# MegaShield-Teensy356-Carrier-v1_0.net
KiCad netlist of a schematic drawn in EAGLE
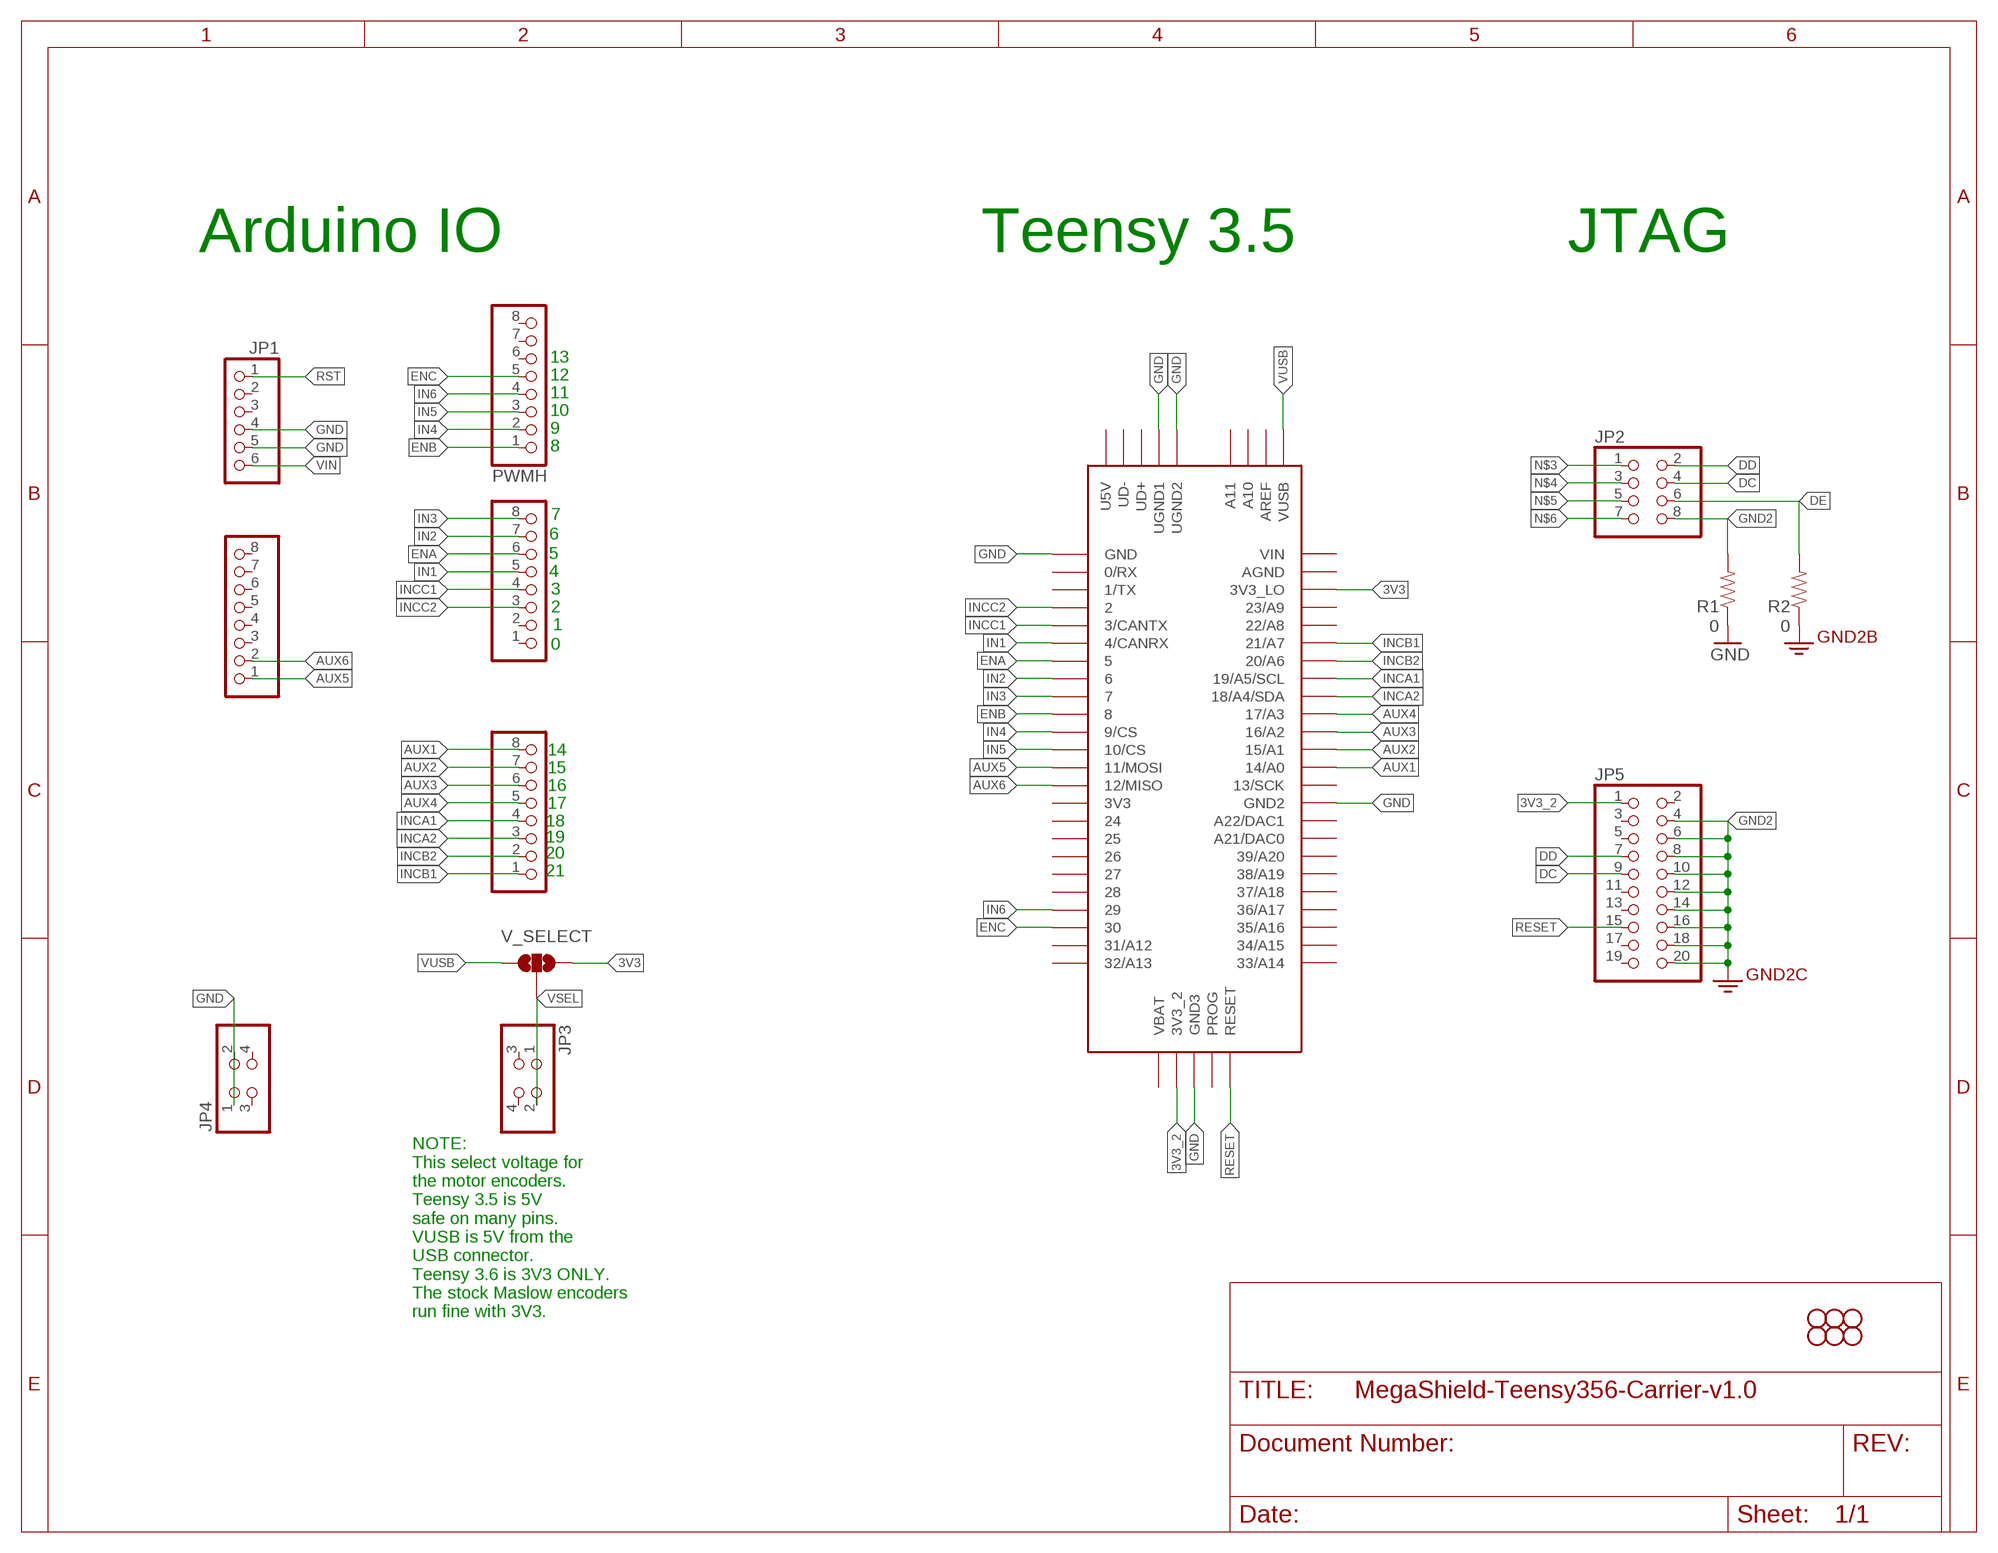
[diagram p0: schematic, sheet 1]

(export (version "E")
  (design (tool "Eeschema 10.0.6"))
  (components
    (comp (ref "COMMUNICATION")
      (value "PINHD-1X8")
      (footprint "eagle-import:1X08")
      (libsource (lib "eagle-import") (part "PINHD-1X8"))
    )
    (comp (ref "COMMUNICATION1")
      (value "PINHD-1X8")
      (footprint "eagle-import:1X08")
      (libsource (lib "eagle-import") (part "PINHD-1X8"))
    )
    (comp (ref "H1")
      (value "STAND-OFF")
      (footprint "eagle-import:STAND-OFF")
      (libsource (lib "eagle-import") (part "STAND-OFF"))
    )
    (comp (ref "H2")
      (value "STAND-OFF")
      (footprint "eagle-import:STAND-OFF")
      (libsource (lib "eagle-import") (part "STAND-OFF"))
    )
    (comp (ref "H3")
      (value "STAND-OFF")
      (footprint "eagle-import:STAND-OFF")
      (libsource (lib "eagle-import") (part "STAND-OFF"))
    )
    (comp (ref "H4")
      (value "STAND-OFF")
      (footprint "eagle-import:STAND-OFF")
      (libsource (lib "eagle-import") (part "STAND-OFF"))
    )
    (comp (ref "H5")
      (value "STAND-OFF")
      (footprint "eagle-import:STAND-OFF")
      (libsource (lib "eagle-import") (part "STAND-OFF"))
    )
    (comp (ref "H6")
      (value "STAND-OFF")
      (footprint "eagle-import:STAND-OFF")
      (libsource (lib "eagle-import") (part "STAND-OFF"))
    )
    (comp (ref "JP1")
      (value "PINHD-1X6")
      (footprint "eagle-import:1X06")
      (libsource (lib "eagle-import") (part "PINHD-1X6"))
    )
    (comp (ref "JP2")
      (value "PINHD-2X4")
      (footprint "eagle-import:2X04")
      (libsource (lib "eagle-import") (part "PINHD-2X4"))
    )
    (comp (ref "JP3")
      (value "PINHD-2X2")
      (footprint "eagle-import:2X02")
      (libsource (lib "eagle-import") (part "PINHD-2X2"))
    )
    (comp (ref "JP4")
      (value "PINHD-2X2")
      (footprint "eagle-import:2X02")
      (libsource (lib "eagle-import") (part "PINHD-2X2"))
    )
    (comp (ref "JP5")
      (value "PINHD-2X10")
      (footprint "eagle-import:2X10")
      (libsource (lib "eagle-import") (part "PINHD-2X10"))
    )
    (comp (ref "PWMH")
      (value "PINHD-1X8")
      (footprint "eagle-import:1X08")
      (libsource (lib "eagle-import") (part "PINHD-1X8"))
    )
    (comp (ref "PWML")
      (value "PINHD-1X8")
      (footprint "eagle-import:1X08")
      (libsource (lib "eagle-import") (part "PINHD-1X8"))
    )
    (comp (ref "R1")
      (value "0")
      (footprint "eagle-import:0603")
      (libsource (lib "eagle-import") (part "0OHM-1/10W-5%(0603)"))
    )
    (comp (ref "R2")
      (value "0")
      (footprint "eagle-import:0603")
      (libsource (lib "eagle-import") (part "0OHM-1/10W-5%(0603)"))
    )
    (comp (ref "U$15")
      (value "TEENSY_3.5/3.6")
      (footprint "eagle-import:TEENSY_3.5_3.6")
      (libsource (lib "eagle-import") (part "TEENSY_3.5/3.6"))
    )
    (comp (ref "V_SELECT")
      (value "SOLDERJUMPER_2WAYT")
      (footprint "eagle-import:SJ_2")
      (libsource (lib "eagle-import") (part "SOLDERJUMPER_2WAYT"))
    )
  )
  (nets
    (net (code "1") (name "3V3") (class "Default")
      (node (ref "U$15") (pin "3V3_LO") (pinfunction "3V3_LO_3V3_LO") (pintype "bidirectional"))
      (node (ref "V_SELECT") (pin "3") (pinfunction "3_3") (pintype "passive"))
    )
    (net (code "2") (name "3V3_2") (class "Default")
      (node (ref "JP5") (pin "1") (pinfunction "1_1") (pintype "passive"))
      (node (ref "U$15") (pin "3V3_2") (pinfunction "3V3_2_3V3_2") (pintype "bidirectional"))
    )
    (net (code "3") (name "AUX1") (class "Default")
      (node (ref "COMMUNICATION") (pin "8") (pinfunction "8_8") (pintype "passive"))
      (node (ref "U$15") (pin "14/A0") (pinfunction "14/A0_14/A0") (pintype "bidirectional"))
    )
    (net (code "4") (name "AUX2") (class "Default")
      (node (ref "COMMUNICATION") (pin "7") (pinfunction "7_7") (pintype "passive"))
      (node (ref "U$15") (pin "15/A1") (pinfunction "15/A1_15/A1") (pintype "bidirectional"))
    )
    (net (code "5") (name "AUX3") (class "Default")
      (node (ref "COMMUNICATION") (pin "6") (pinfunction "6_6") (pintype "passive"))
      (node (ref "U$15") (pin "16/A2") (pinfunction "16/A2_16/A2") (pintype "bidirectional"))
    )
    (net (code "6") (name "AUX4") (class "Default")
      (node (ref "COMMUNICATION") (pin "5") (pinfunction "5_5") (pintype "passive"))
      (node (ref "U$15") (pin "17/A3") (pinfunction "17/A3_17/A3") (pintype "bidirectional"))
    )
    (net (code "7") (name "AUX5") (class "Default")
      (node (ref "COMMUNICATION1") (pin "1") (pinfunction "1_1") (pintype "passive"))
      (node (ref "U$15") (pin "11/MOSI") (pinfunction "11/MOSI_11/MOSI") (pintype "bidirectional"))
    )
    (net (code "8") (name "AUX6") (class "Default")
      (node (ref "COMMUNICATION1") (pin "2") (pinfunction "2_2") (pintype "passive"))
      (node (ref "U$15") (pin "12/MISO") (pinfunction "12/MISO_12/MISO") (pintype "bidirectional"))
    )
    (net (code "9") (name "DC") (class "Default")
      (node (ref "JP2") (pin "4") (pinfunction "4_4") (pintype "passive"))
      (node (ref "JP5") (pin "9") (pinfunction "9_9") (pintype "passive"))
    )
    (net (code "10") (name "DD") (class "Default")
      (node (ref "JP2") (pin "2") (pinfunction "2_2") (pintype "passive"))
      (node (ref "JP5") (pin "7") (pinfunction "7_7") (pintype "passive"))
    )
    (net (code "11") (name "DE") (class "Default")
      (node (ref "JP2") (pin "6") (pinfunction "6_6") (pintype "passive"))
      (node (ref "R2") (pin "2") (pinfunction "2_2") (pintype "passive"))
    )
    (net (code "12") (name "ENA") (class "Default")
      (node (ref "PWML") (pin "6") (pinfunction "6_6") (pintype "passive"))
      (node (ref "U$15") (pin "5") (pinfunction "5_5") (pintype "bidirectional"))
    )
    (net (code "13") (name "ENB") (class "Default")
      (node (ref "PWMH") (pin "1") (pinfunction "1_1") (pintype "passive"))
      (node (ref "U$15") (pin "8") (pinfunction "8_8") (pintype "bidirectional"))
    )
    (net (code "14") (name "ENC") (class "Default")
      (node (ref "PWMH") (pin "5") (pinfunction "5_5") (pintype "passive"))
      (node (ref "U$15") (pin "30") (pinfunction "30_30") (pintype "bidirectional"))
    )
    (net (code "15") (name "GND") (class "Default")
      (node (ref "JP1") (pin "4") (pinfunction "4_4") (pintype "passive"))
      (node (ref "JP1") (pin "5") (pinfunction "5_5") (pintype "passive"))
      (node (ref "JP4") (pin "1") (pinfunction "1_1") (pintype "passive"))
      (node (ref "JP4") (pin "2") (pinfunction "2_2") (pintype "passive"))
      (node (ref "R1") (pin "1") (pinfunction "1_1") (pintype "passive"))
      (node (ref "U$15") (pin "GND") (pinfunction "GND_GND") (pintype "bidirectional"))
      (node (ref "U$15") (pin "GND2") (pinfunction "GND2_GND2") (pintype "bidirectional"))
      (node (ref "U$15") (pin "GND3") (pinfunction "GND3_GND3") (pintype "bidirectional"))
      (node (ref "U$15") (pin "UGND1") (pinfunction "UGND1_UGND1") (pintype "bidirectional"))
      (node (ref "U$15") (pin "UGND2") (pinfunction "UGND2_UGND2") (pintype "bidirectional"))
    )
    (net (code "16") (name "GND2") (class "Default")
      (node (ref "JP2") (pin "8") (pinfunction "8_8") (pintype "passive"))
      (node (ref "JP5") (pin "10") (pinfunction "10_10") (pintype "passive"))
      (node (ref "JP5") (pin "12") (pinfunction "12_12") (pintype "passive"))
      (node (ref "JP5") (pin "14") (pinfunction "14_14") (pintype "passive"))
      (node (ref "JP5") (pin "16") (pinfunction "16_16") (pintype "passive"))
      (node (ref "JP5") (pin "18") (pinfunction "18_18") (pintype "passive"))
      (node (ref "JP5") (pin "20") (pinfunction "20_20") (pintype "passive"))
      (node (ref "JP5") (pin "4") (pinfunction "4_4") (pintype "passive"))
      (node (ref "JP5") (pin "6") (pinfunction "6_6") (pintype "passive"))
      (node (ref "JP5") (pin "8") (pinfunction "8_8") (pintype "passive"))
      (node (ref "R1") (pin "2") (pinfunction "2_2") (pintype "passive"))
      (node (ref "R2") (pin "1") (pinfunction "1_1") (pintype "passive"))
    )
    (net (code "17") (name "IN1") (class "Default")
      (node (ref "PWML") (pin "5") (pinfunction "5_5") (pintype "passive"))
      (node (ref "U$15") (pin "4/CANRX") (pinfunction "4/CANRX_4/CANRX") (pintype "bidirectional"))
    )
    (net (code "18") (name "IN2") (class "Default")
      (node (ref "PWML") (pin "7") (pinfunction "7_7") (pintype "passive"))
      (node (ref "U$15") (pin "6") (pinfunction "6_6") (pintype "bidirectional"))
    )
    (net (code "19") (name "IN3") (class "Default")
      (node (ref "PWML") (pin "8") (pinfunction "8_8") (pintype "passive"))
      (node (ref "U$15") (pin "7") (pinfunction "7_7") (pintype "bidirectional"))
    )
    (net (code "20") (name "IN4") (class "Default")
      (node (ref "PWMH") (pin "2") (pinfunction "2_2") (pintype "passive"))
      (node (ref "U$15") (pin "9/CS") (pinfunction "9/CS_9/CS") (pintype "bidirectional"))
    )
    (net (code "21") (name "IN5") (class "Default")
      (node (ref "PWMH") (pin "3") (pinfunction "3_3") (pintype "passive"))
      (node (ref "U$15") (pin "10/CS") (pinfunction "10/CS_10/CS") (pintype "bidirectional"))
    )
    (net (code "22") (name "IN6") (class "Default")
      (node (ref "PWMH") (pin "4") (pinfunction "4_4") (pintype "passive"))
      (node (ref "U$15") (pin "29") (pinfunction "29_29") (pintype "bidirectional"))
    )
    (net (code "23") (name "INCA1") (class "Default")
      (node (ref "COMMUNICATION") (pin "4") (pinfunction "4_4") (pintype "passive"))
      (node (ref "U$15") (pin "19/A5/SCL") (pinfunction "19/A5/SCL_19/A5/SCL") (pintype "bidirectional"))
    )
    (net (code "24") (name "INCA2") (class "Default")
      (node (ref "COMMUNICATION") (pin "3") (pinfunction "3_3") (pintype "passive"))
      (node (ref "U$15") (pin "18/A4/SDA") (pinfunction "18/A4/SDA_18/A4/SDA") (pintype "bidirectional"))
    )
    (net (code "25") (name "INCB1") (class "Default")
      (node (ref "COMMUNICATION") (pin "1") (pinfunction "1_1") (pintype "passive"))
      (node (ref "U$15") (pin "21/A7") (pinfunction "21/A7_21/A7") (pintype "bidirectional"))
    )
    (net (code "26") (name "INCB2") (class "Default")
      (node (ref "COMMUNICATION") (pin "2") (pinfunction "2_2") (pintype "passive"))
      (node (ref "U$15") (pin "20/A6") (pinfunction "20/A6_20/A6") (pintype "bidirectional"))
    )
    (net (code "27") (name "INCC1") (class "Default")
      (node (ref "PWML") (pin "4") (pinfunction "4_4") (pintype "passive"))
      (node (ref "U$15") (pin "3/CANTX") (pinfunction "3/CANTX_3/CANTX") (pintype "bidirectional"))
    )
    (net (code "28") (name "INCC2") (class "Default")
      (node (ref "PWML") (pin "3") (pinfunction "3_3") (pintype "passive"))
      (node (ref "U$15") (pin "2") (pinfunction "2_2") (pintype "bidirectional"))
    )
    (net (code "29") (name "N$3") (class "Default")
      (node (ref "JP2") (pin "1") (pinfunction "1_1") (pintype "passive"))
    )
    (net (code "30") (name "N$4") (class "Default")
      (node (ref "JP2") (pin "3") (pinfunction "3_3") (pintype "passive"))
    )
    (net (code "31") (name "N$5") (class "Default")
      (node (ref "JP2") (pin "5") (pinfunction "5_5") (pintype "passive"))
    )
    (net (code "32") (name "N$6") (class "Default")
      (node (ref "JP2") (pin "7") (pinfunction "7_7") (pintype "passive"))
    )
    (net (code "33") (name "RESET") (class "Default")
      (node (ref "JP5") (pin "15") (pinfunction "15_15") (pintype "passive"))
      (node (ref "U$15") (pin "RESET") (pinfunction "RESET_RESET") (pintype "bidirectional"))
    )
    (net (code "34") (name "RST") (class "Default")
      (node (ref "JP1") (pin "1") (pinfunction "1_1") (pintype "passive"))
    )
    (net (code "35") (name "VIN") (class "Default")
      (node (ref "JP1") (pin "6") (pinfunction "6_6") (pintype "passive"))
    )
    (net (code "36") (name "VSEL") (class "Default")
      (node (ref "JP3") (pin "1") (pinfunction "1_1") (pintype "passive"))
      (node (ref "JP3") (pin "2") (pinfunction "2_2") (pintype "passive"))
      (node (ref "V_SELECT") (pin "2") (pinfunction "2_2") (pintype "passive"))
    )
    (net (code "37") (name "VUSB") (class "Default")
      (node (ref "U$15") (pin "VUSB") (pinfunction "VUSB_VUSB") (pintype "bidirectional"))
      (node (ref "V_SELECT") (pin "1") (pinfunction "1_1") (pintype "passive"))
    )
    (net (code "38") (name "unconnected-(COMMUNICATION1-Pad3)") (class "Default")
      (node (ref "COMMUNICATION1") (pin "3") (pinfunction "3_3") (pintype "passive"))
    )
    (net (code "39") (name "unconnected-(COMMUNICATION1-Pad4)") (class "Default")
      (node (ref "COMMUNICATION1") (pin "4") (pinfunction "4_4") (pintype "passive"))
    )
    (net (code "40") (name "unconnected-(COMMUNICATION1-Pad5)") (class "Default")
      (node (ref "COMMUNICATION1") (pin "5") (pinfunction "5_5") (pintype "passive"))
    )
    (net (code "41") (name "unconnected-(COMMUNICATION1-Pad6)") (class "Default")
      (node (ref "COMMUNICATION1") (pin "6") (pinfunction "6_6") (pintype "passive"))
    )
    (net (code "42") (name "unconnected-(COMMUNICATION1-Pad7)") (class "Default")
      (node (ref "COMMUNICATION1") (pin "7") (pinfunction "7_7") (pintype "passive"))
    )
    (net (code "43") (name "unconnected-(COMMUNICATION1-Pad8)") (class "Default")
      (node (ref "COMMUNICATION1") (pin "8") (pinfunction "8_8") (pintype "passive"))
    )
    (net (code "44") (name "unconnected-(JP1-Pad2)") (class "Default")
      (node (ref "JP1") (pin "2") (pinfunction "2_2") (pintype "passive"))
    )
    (net (code "45") (name "unconnected-(JP1-Pad3)") (class "Default")
      (node (ref "JP1") (pin "3") (pinfunction "3_3") (pintype "passive"))
    )
    (net (code "46") (name "unconnected-(JP3-Pad3)") (class "Default")
      (node (ref "JP3") (pin "3") (pinfunction "3_3") (pintype "passive"))
    )
    (net (code "47") (name "unconnected-(JP3-Pad4)") (class "Default")
      (node (ref "JP3") (pin "4") (pinfunction "4_4") (pintype "passive"))
    )
    (net (code "48") (name "unconnected-(JP4-Pad3)") (class "Default")
      (node (ref "JP4") (pin "3") (pinfunction "3_3") (pintype "passive"))
    )
    (net (code "49") (name "unconnected-(JP4-Pad4)") (class "Default")
      (node (ref "JP4") (pin "4") (pinfunction "4_4") (pintype "passive"))
    )
    (net (code "50") (name "unconnected-(JP5-Pad2)") (class "Default")
      (node (ref "JP5") (pin "2") (pinfunction "2_2") (pintype "passive"))
    )
    (net (code "51") (name "unconnected-(JP5-Pad3)") (class "Default")
      (node (ref "JP5") (pin "3") (pinfunction "3_3") (pintype "passive"))
    )
    (net (code "52") (name "unconnected-(JP5-Pad5)") (class "Default")
      (node (ref "JP5") (pin "5") (pinfunction "5_5") (pintype "passive"))
    )
    (net (code "53") (name "unconnected-(JP5-Pad11)") (class "Default")
      (node (ref "JP5") (pin "11") (pinfunction "11_11") (pintype "passive"))
    )
    (net (code "54") (name "unconnected-(JP5-Pad13)") (class "Default")
      (node (ref "JP5") (pin "13") (pinfunction "13_13") (pintype "passive"))
    )
    (net (code "55") (name "unconnected-(JP5-Pad17)") (class "Default")
      (node (ref "JP5") (pin "17") (pinfunction "17_17") (pintype "passive"))
    )
    (net (code "56") (name "unconnected-(JP5-Pad19)") (class "Default")
      (node (ref "JP5") (pin "19") (pinfunction "19_19") (pintype "passive"))
    )
    (net (code "57") (name "unconnected-(PWMH-Pad6)") (class "Default")
      (node (ref "PWMH") (pin "6") (pinfunction "6_6") (pintype "passive"))
    )
    (net (code "58") (name "unconnected-(PWMH-Pad7)") (class "Default")
      (node (ref "PWMH") (pin "7") (pinfunction "7_7") (pintype "passive"))
    )
    (net (code "59") (name "unconnected-(PWMH-Pad8)") (class "Default")
      (node (ref "PWMH") (pin "8") (pinfunction "8_8") (pintype "passive"))
    )
    (net (code "60") (name "unconnected-(PWML-Pad1)") (class "Default")
      (node (ref "PWML") (pin "1") (pinfunction "1_1") (pintype "passive"))
    )
    (net (code "61") (name "unconnected-(PWML-Pad2)") (class "Default")
      (node (ref "PWML") (pin "2") (pinfunction "2_2") (pintype "passive"))
    )
    (net (code "62") (name "unconnected-(U$15-A21{slash}DAC0-Pad21{slash}DAC0)") (class "Default")
      (node (ref "U$15") (pin "21/DAC0") (pinfunction "A21/DAC0_21/DAC0") (pintype "bidirectional"))
    )
    (net (code "63") (name "unconnected-(U$15-Pad0{slash}RX)") (class "Default")
      (node (ref "U$15") (pin "0/RX") (pinfunction "0/RX_0/RX") (pintype "bidirectional"))
    )
    (net (code "64") (name "unconnected-(U$15-Pad1{slash}TX)") (class "Default")
      (node (ref "U$15") (pin "1/TX") (pinfunction "1/TX_1/TX") (pintype "bidirectional"))
    )
    (net (code "65") (name "unconnected-(U$15-Pad3V3)") (class "Default")
      (node (ref "U$15") (pin "3V3") (pinfunction "3V3_3V3") (pintype "bidirectional"))
    )
    (net (code "66") (name "unconnected-(U$15-Pad13{slash}SCK)") (class "Default")
      (node (ref "U$15") (pin "13/SCK") (pinfunction "13/SCK_13/SCK") (pintype "bidirectional"))
    )
    (net (code "67") (name "unconnected-(U$15-Pad22{slash}A8)") (class "Default")
      (node (ref "U$15") (pin "22/A8") (pinfunction "22/A8_22/A8") (pintype "bidirectional"))
    )
    (net (code "68") (name "unconnected-(U$15-Pad23{slash}A9)") (class "Default")
      (node (ref "U$15") (pin "23/A9") (pinfunction "23/A9_23/A9") (pintype "bidirectional"))
    )
    (net (code "69") (name "unconnected-(U$15-Pad24)") (class "Default")
      (node (ref "U$15") (pin "24") (pinfunction "24_24") (pintype "bidirectional"))
    )
    (net (code "70") (name "unconnected-(U$15-Pad25)") (class "Default")
      (node (ref "U$15") (pin "25") (pinfunction "25_25") (pintype "bidirectional"))
    )
    (net (code "71") (name "unconnected-(U$15-Pad26)") (class "Default")
      (node (ref "U$15") (pin "26") (pinfunction "26_26") (pintype "bidirectional"))
    )
    (net (code "72") (name "unconnected-(U$15-Pad27)") (class "Default")
      (node (ref "U$15") (pin "27") (pinfunction "27_27") (pintype "bidirectional"))
    )
    (net (code "73") (name "unconnected-(U$15-Pad28)") (class "Default")
      (node (ref "U$15") (pin "28") (pinfunction "28_28") (pintype "bidirectional"))
    )
    (net (code "74") (name "unconnected-(U$15-Pad31{slash}A12)") (class "Default")
      (node (ref "U$15") (pin "31/A12") (pinfunction "31/A12_31/A12") (pintype "bidirectional"))
    )
    (net (code "75") (name "unconnected-(U$15-Pad32{slash}A13)") (class "Default")
      (node (ref "U$15") (pin "32/A13") (pinfunction "32/A13_32/A13") (pintype "bidirectional"))
    )
    (net (code "76") (name "unconnected-(U$15-Pad33{slash}A14)") (class "Default")
      (node (ref "U$15") (pin "33/A14") (pinfunction "33/A14_33/A14") (pintype "bidirectional"))
    )
    (net (code "77") (name "unconnected-(U$15-Pad34{slash}A15)") (class "Default")
      (node (ref "U$15") (pin "34/A15") (pinfunction "34/A15_34/A15") (pintype "bidirectional"))
    )
    (net (code "78") (name "unconnected-(U$15-Pad35{slash}A16)") (class "Default")
      (node (ref "U$15") (pin "35/A16") (pinfunction "35/A16_35/A16") (pintype "bidirectional"))
    )
    (net (code "79") (name "unconnected-(U$15-Pad36{slash}A17)") (class "Default")
      (node (ref "U$15") (pin "36/A17") (pinfunction "36/A17_36/A17") (pintype "bidirectional"))
    )
    (net (code "80") (name "unconnected-(U$15-Pad37{slash}A18)") (class "Default")
      (node (ref "U$15") (pin "37/A18") (pinfunction "37/A18_37/A18") (pintype "bidirectional"))
    )
    (net (code "81") (name "unconnected-(U$15-Pad38{slash}A19)") (class "Default")
      (node (ref "U$15") (pin "38/A19") (pinfunction "38/A19_38/A19") (pintype "bidirectional"))
    )
    (net (code "82") (name "unconnected-(U$15-Pad39{slash}A20)") (class "Default")
      (node (ref "U$15") (pin "39/A20") (pinfunction "39/A20_39/A20") (pintype "bidirectional"))
    )
    (net (code "83") (name "unconnected-(U$15-PadA10)") (class "Default")
      (node (ref "U$15") (pin "A10") (pinfunction "A10_A10") (pintype "bidirectional"))
    )
    (net (code "84") (name "unconnected-(U$15-PadA11)") (class "Default")
      (node (ref "U$15") (pin "A11") (pinfunction "A11_A11") (pintype "bidirectional"))
    )
    (net (code "85") (name "unconnected-(U$15-PadA22{slash}DAC1)") (class "Default")
      (node (ref "U$15") (pin "A22/DAC1") (pinfunction "A22/DAC1_A22/DAC1") (pintype "bidirectional"))
    )
    (net (code "86") (name "unconnected-(U$15-PadAGND)") (class "Default")
      (node (ref "U$15") (pin "AGND") (pinfunction "AGND_AGND") (pintype "bidirectional"))
    )
    (net (code "87") (name "unconnected-(U$15-PadAREF)") (class "Default")
      (node (ref "U$15") (pin "AREF") (pinfunction "AREF_AREF") (pintype "bidirectional"))
    )
    (net (code "88") (name "unconnected-(U$15-PadPROG)") (class "Default")
      (node (ref "U$15") (pin "PROG") (pinfunction "PROG_PROG") (pintype "bidirectional"))
    )
    (net (code "89") (name "unconnected-(U$15-PadU5V)") (class "Default")
      (node (ref "U$15") (pin "U5V") (pinfunction "U5V_U5V") (pintype "bidirectional"))
    )
    (net (code "90") (name "unconnected-(U$15-PadUD+)") (class "Default")
      (node (ref "U$15") (pin "UD+") (pinfunction "UD+_UD+") (pintype "bidirectional"))
    )
    (net (code "91") (name "unconnected-(U$15-PadUD-)") (class "Default")
      (node (ref "U$15") (pin "UD-") (pinfunction "UD-_UD-") (pintype "bidirectional"))
    )
    (net (code "92") (name "unconnected-(U$15-PadVBAT)") (class "Default")
      (node (ref "U$15") (pin "VBAT") (pinfunction "VBAT_VBAT") (pintype "bidirectional"))
    )
    (net (code "93") (name "unconnected-(U$15-PadVIN)") (class "Default")
      (node (ref "U$15") (pin "VIN") (pinfunction "VIN_VIN") (pintype "bidirectional"))
    )
  )
)
